# Analog.net
KiCad netlist of a schematic drawn in Altium Designer
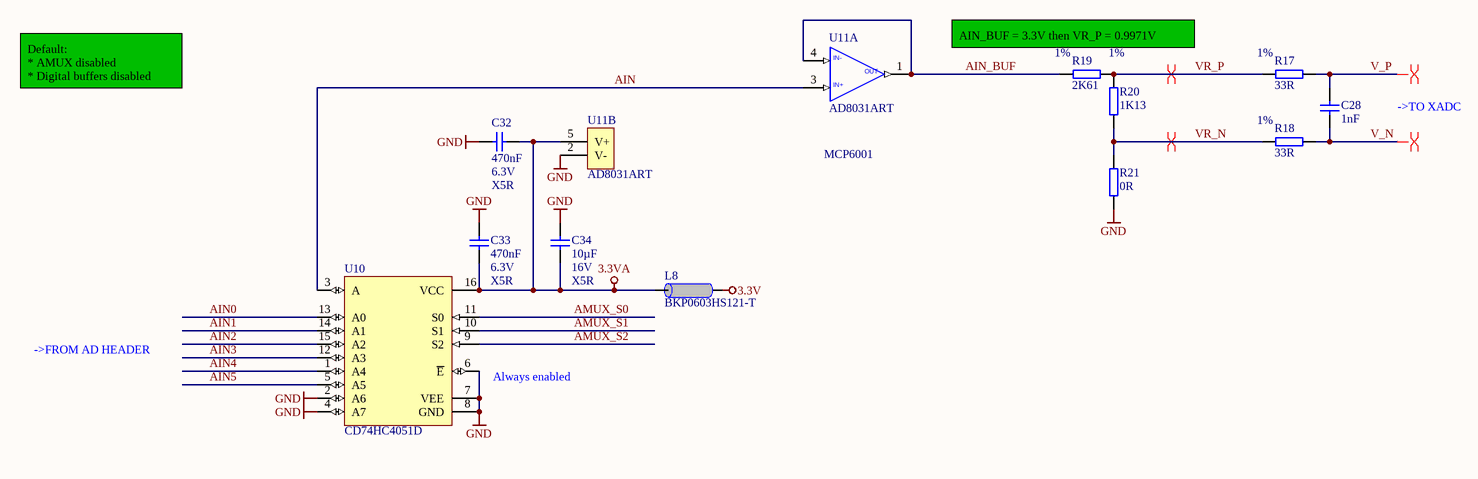
[diagram p0: Analog.SchDoc]

(export (version "E")
  (design (tool "Eeschema 10.0.6"))
  (components
    (comp (ref "C28")
      (value "1nF")
      (footprint "CAPC1005X55N")
      (description "KON 1nF 50V SMD AEC-Q200")
      (fields (field (name "VOLTAGE") "50V") (field (name "TOLERANCE") "10%"))
      (libsource (lib "TE") (part "CAP-NP"))
    )
    (comp (ref "C32")
      (value "470nF")
      (footprint "CAPC0603X33N")
      (description "KON 470nF X5R 6.3V SMD 20%")
      (fields
        (field (name "VOLTAGE") "6.3V")
        (field (name "TECHNOLOGY") "X5R")
        (field (name "TOLERANCE") "20%")
      )
      (libsource (lib "TE") (part "CAP-NP"))
    )
    (comp (ref "C33")
      (value "470nF")
      (footprint "CAPC0603X33N")
      (description "KON 470nF X5R 6.3V SMD 20%")
      (fields
        (field (name "VOLTAGE") "6.3V")
        (field (name "TECHNOLOGY") "X5R")
        (field (name "TOLERANCE") "20%")
      )
      (libsource (lib "TE") (part "CAP-NP"))
    )
    (comp (ref "C34")
      (value "10µF")
      (footprint "CAPC1608X90N")
      (description "KON 10µF 16V X5R SMD 20%")
      (fields
        (field (name "VOLTAGE") "16V")
        (field (name "TECHNOLOGY") "X5R")
        (field (name "TOLERANCE") "20%")
      )
      (libsource (lib "TE") (part "CAP-NP"))
    )
    (comp (ref "L8")
      (value "BKP0603HS121-T")
      (footprint "INDC0603X33N")
      (description "Ferritdurchführung SMD 0201")
      (fields (field (name "TOLERANCE") "25%"))
      (libsource (lib "TE") (part "Ferritperle"))
    )
    (comp (ref "R17")
      (value "33R")
      (footprint "RESC0603X26N")
      (description "WID SMD 33R 1% 0,05W")
      (fields (field (name "TOLERANCE") "1%"))
      (libsource (lib "TE") (part "RES"))
    )
    (comp (ref "R18")
      (value "33R")
      (footprint "RESC0603X26N")
      (description "WID SMD 33R 1% 0,05W")
      (fields (field (name "TOLERANCE") "1%"))
      (libsource (lib "TE") (part "RES"))
    )
    (comp (ref "R19")
      (value "2K61")
      (footprint "RESC1005X40N")
      (description "WID SMD 2K61 1% 0,063W")
      (fields (field (name "TOLERANCE") "1%"))
      (libsource (lib "TE") (part "RES"))
    )
    (comp (ref "R20")
      (value "1K13")
      (footprint "RESC1005X40N")
      (description "WID SMD 1K13 1% 0,063W")
      (fields (field (name "TOLERANCE") "1%"))
      (libsource (lib "TE") (part "RES"))
    )
    (comp (ref "R21")
      (value "0R")
      (footprint "RESC1005X40N")
      (description "WID SMD 0R 1% 0.063W AEC-Q200")
      (libsource (lib "TE") (part "RES"))
    )
    (comp (ref "U10")
      (value "CD74HC4051D")
      (footprint "SOIC127P600X175-16N")
      (libsource (lib "TE") (part "CD74HCT4051"))
    )
    (comp (ref "U11")
      (value "AD8031ART")
      (footprint "SOT95P280X145-5N")
      (libsource (lib "TE") (part "AD8031xRT"))
    )
  )
  (nets
    (net (code "1") (name "/AIN") (class "Default")
      (node (ref "U10") (pin "3") (pinfunction "A_3") (pintype "bidirectional"))
      (node (ref "U11") (pin "3") (pinfunction "IN+_3") (pintype "input"))
    )
    (net (code "2") (name "/AIN0") (class "Default")
      (node (ref "U10") (pin "13") (pinfunction "A0_13") (pintype "bidirectional"))
    )
    (net (code "3") (name "/AIN1") (class "Default")
      (node (ref "U10") (pin "14") (pinfunction "A1_14") (pintype "bidirectional"))
    )
    (net (code "4") (name "/AIN2") (class "Default")
      (node (ref "U10") (pin "15") (pinfunction "A2_15") (pintype "bidirectional"))
    )
    (net (code "5") (name "/AIN3") (class "Default")
      (node (ref "U10") (pin "12") (pinfunction "A3_12") (pintype "bidirectional"))
    )
    (net (code "6") (name "/AIN4") (class "Default")
      (node (ref "U10") (pin "1") (pinfunction "A4_1") (pintype "bidirectional"))
    )
    (net (code "7") (name "/AIN5") (class "Default")
      (node (ref "U10") (pin "5") (pinfunction "A5_5") (pintype "bidirectional"))
    )
    (net (code "8") (name "/AIN_BUF") (class "Default")
      (node (ref "R19") (pin "1") (pinfunction "1_1") (pintype "passive"))
      (node (ref "U11") (pin "1") (pinfunction "OUT_1") (pintype "output"))
      (node (ref "U11") (pin "4") (pinfunction "IN-_4") (pintype "input"))
    )
    (net (code "9") (name "/AMUX_S0") (class "Default")
      (node (ref "U10") (pin "11") (pinfunction "S0_11") (pintype "input"))
    )
    (net (code "10") (name "/AMUX_S1") (class "Default")
      (node (ref "U10") (pin "10") (pinfunction "S1_10") (pintype "input"))
    )
    (net (code "11") (name "/AMUX_S2") (class "Default")
      (node (ref "U10") (pin "9") (pinfunction "S2_9") (pintype "input"))
    )
    (net (code "12") (name "/VR_N") (class "Default")
      (node (ref "R18") (pin "1") (pinfunction "1_1") (pintype "passive"))
      (node (ref "R20") (pin "2") (pinfunction "2_2") (pintype "passive"))
      (node (ref "R21") (pin "1") (pinfunction "1_1") (pintype "passive"))
    )
    (net (code "13") (name "/VR_P") (class "Default")
      (node (ref "R17") (pin "1") (pinfunction "1_1") (pintype "passive"))
      (node (ref "R19") (pin "2") (pinfunction "2_2") (pintype "passive"))
      (node (ref "R20") (pin "1") (pinfunction "1_1") (pintype "passive"))
    )
    (net (code "14") (name "/V_N") (class "Default")
      (node (ref "C28") (pin "2") (pinfunction "2_2") (pintype "passive"))
      (node (ref "R18") (pin "2") (pinfunction "2_2") (pintype "passive"))
    )
    (net (code "15") (name "/V_P") (class "Default")
      (node (ref "C28") (pin "1") (pinfunction "1_1") (pintype "passive"))
      (node (ref "R17") (pin "2") (pinfunction "2_2") (pintype "passive"))
    )
    (net (code "16") (name "3.3V") (class "Default")
      (node (ref "L8") (pin "1") (pinfunction "1_1") (pintype "passive"))
    )
    (net (code "17") (name "3.3VA") (class "Default")
      (node (ref "C32") (pin "2") (pinfunction "2_2") (pintype "passive"))
      (node (ref "C33") (pin "1") (pinfunction "1_1") (pintype "passive"))
      (node (ref "C34") (pin "2") (pinfunction "2_2") (pintype "passive"))
      (node (ref "L8") (pin "2") (pinfunction "2_2") (pintype "passive"))
      (node (ref "U10") (pin "16") (pinfunction "VCC_16") (pintype "power_in"))
      (node (ref "U11") (pin "5") (pinfunction "V+_5") (pintype "power_in"))
    )
    (net (code "18") (name "GND") (class "Default")
      (node (ref "C32") (pin "1") (pinfunction "1_1") (pintype "passive"))
      (node (ref "C33") (pin "2") (pinfunction "2_2") (pintype "passive"))
      (node (ref "C34") (pin "1") (pinfunction "1_1") (pintype "passive"))
      (node (ref "R21") (pin "2") (pinfunction "2_2") (pintype "passive"))
      (node (ref "U10") (pin "2") (pinfunction "A6_2") (pintype "bidirectional"))
      (node (ref "U10") (pin "4") (pinfunction "A7_4") (pintype "bidirectional"))
      (node (ref "U10") (pin "6") (pinfunction "~{E}_6") (pintype "bidirectional"))
      (node (ref "U10") (pin "7") (pinfunction "VEE_7") (pintype "power_in"))
      (node (ref "U10") (pin "8") (pinfunction "GND_8") (pintype "power_in"))
      (node (ref "U11") (pin "2") (pinfunction "V-_2") (pintype "power_in"))
    )
  )
)
